# 03_ADC.net
KiCad netlist of a schematic drawn in Altium Designer
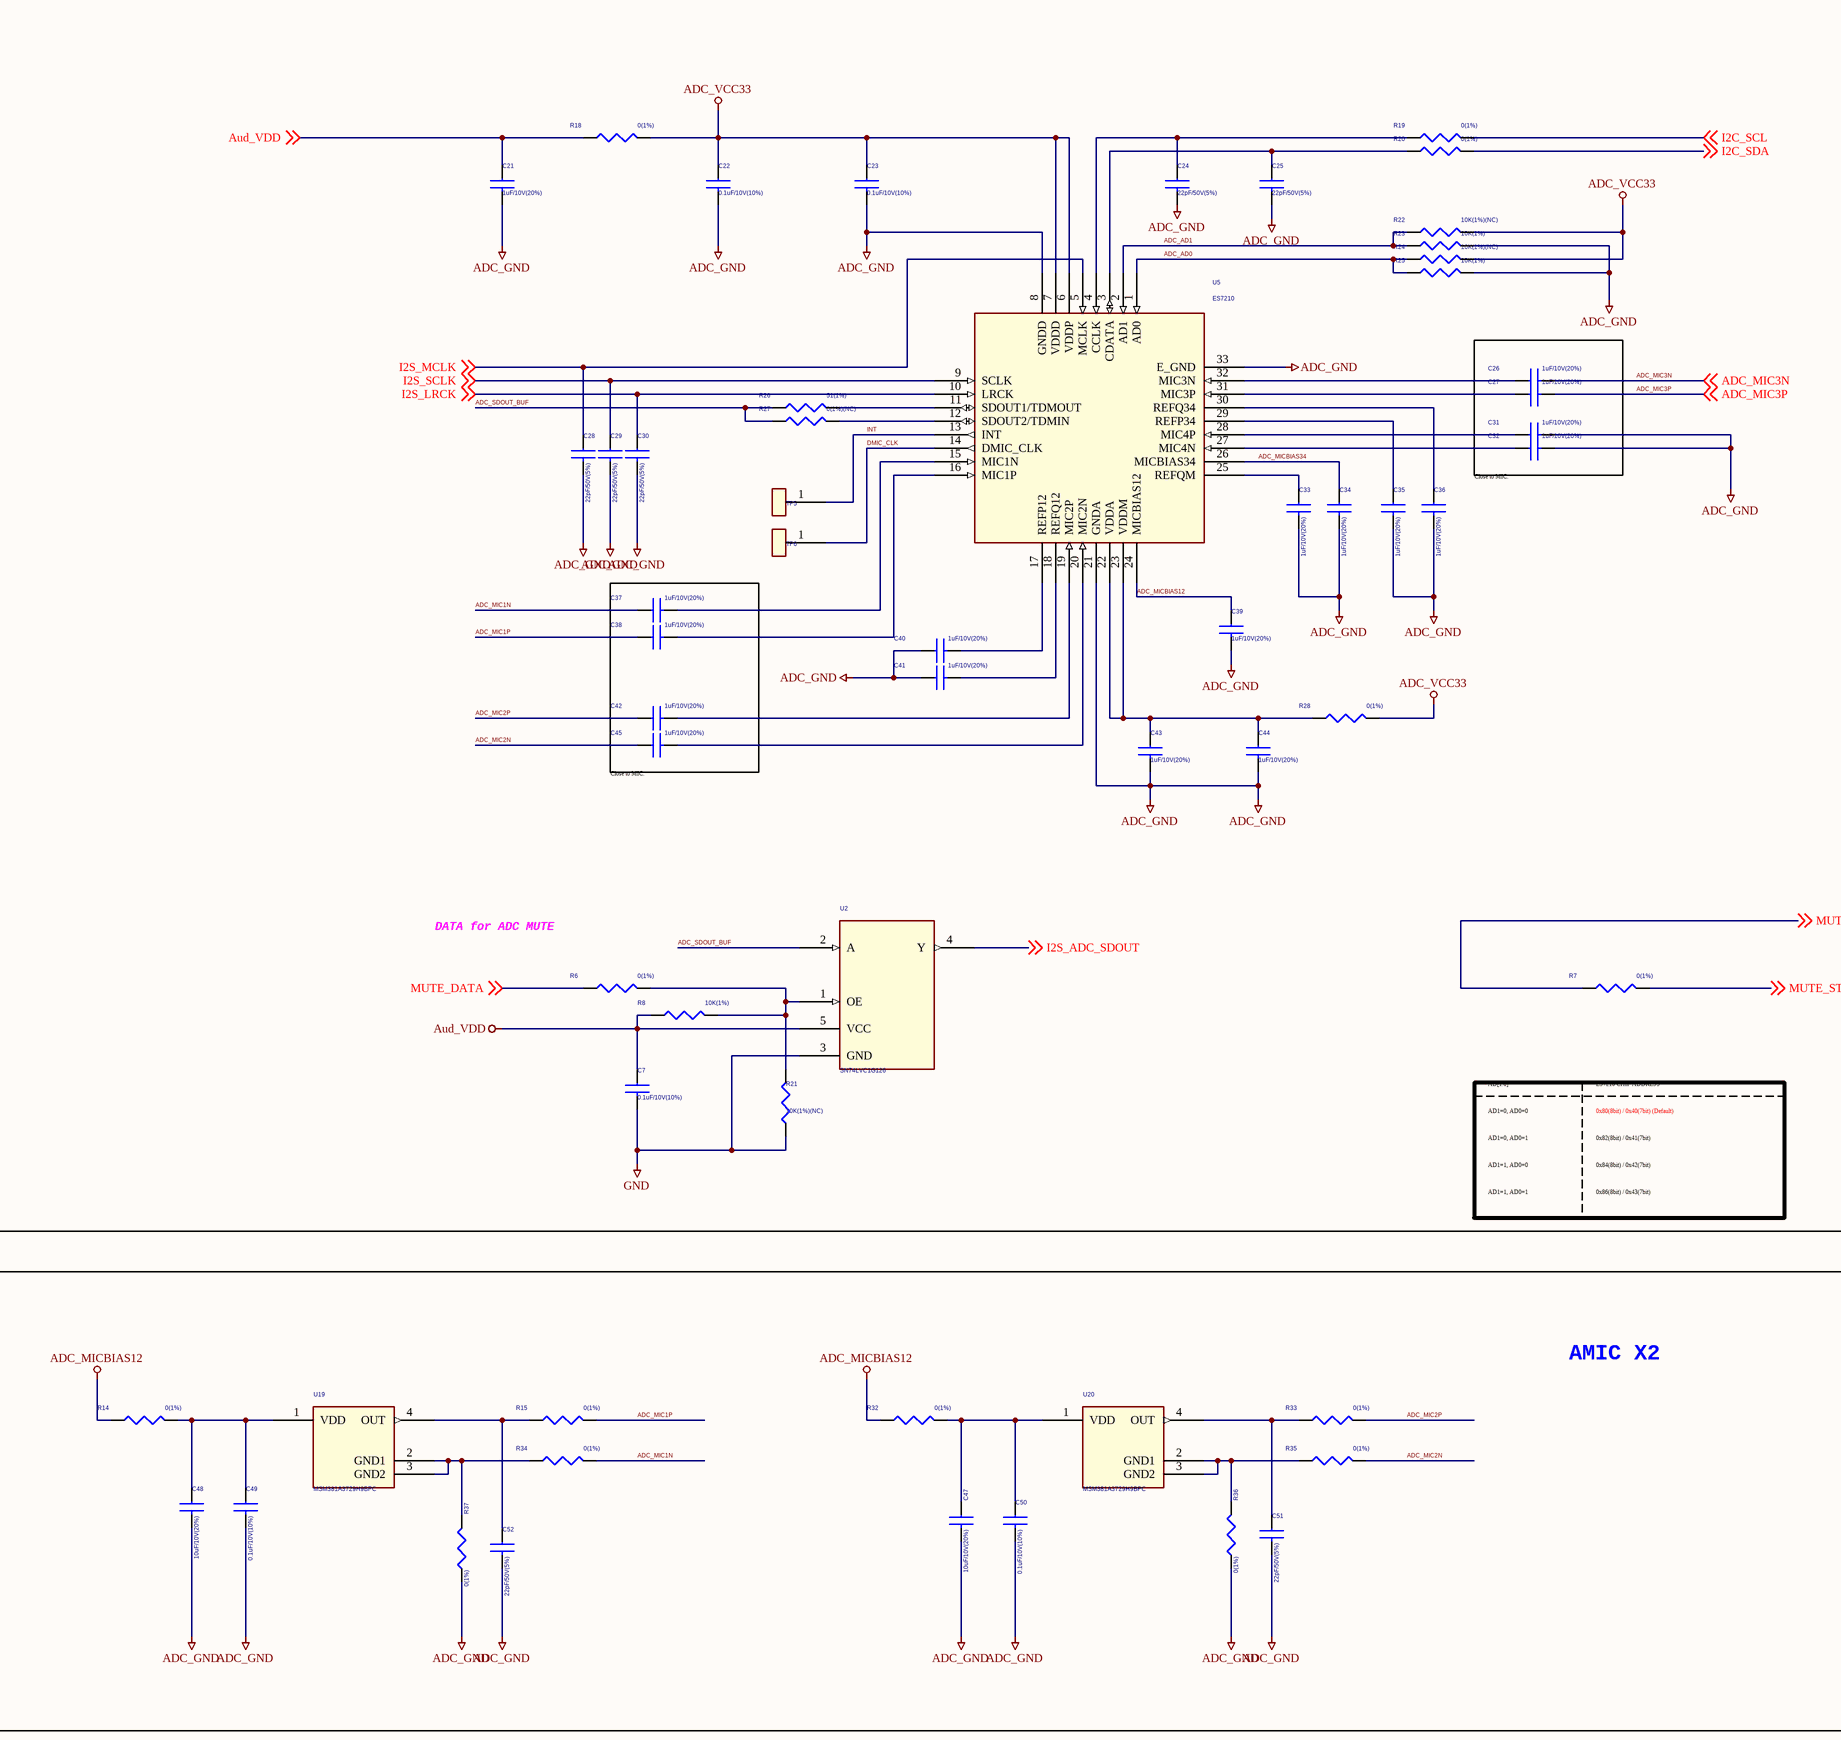
[diagram p0: 03_ADC.SchDoc, left]
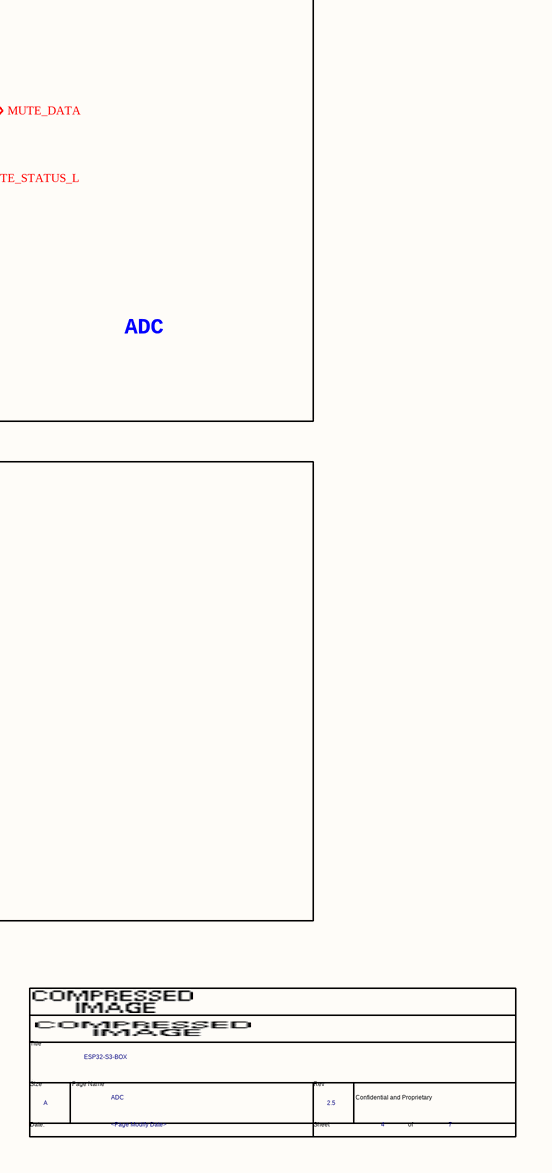
[diagram p1: 03_ADC.SchDoc, right]

(export (version "E")
  (design (tool "Eeschema 10.0.6"))
  (components
    (comp (ref "C7")
      (value "0.1uF/10V(10%)")
      (footprint "0201_C")
      (fields (field (name "PART NUMBER") "ES11025103610001"))
      (libsource (lib "*") (part "CAPACITOR"))
    )
    (comp (ref "C21")
      (value "1uF/10V(20%)")
      (footprint "0201_C")
      (fields (field (name "PART NUMBER") "ES11026103700001"))
      (libsource (lib "*") (part "CAPACITOR"))
    )
    (comp (ref "C22")
      (value "0.1uF/10V(10%)")
      (footprint "0201_C")
      (fields (field (name "PART NUMBER") "ES11025103610001"))
      (libsource (lib "*") (part "CAPACITOR"))
    )
    (comp (ref "C23")
      (value "0.1uF/10V(10%)")
      (footprint "0201_C")
      (fields (field (name "PART NUMBER") "ES11025103610001"))
      (libsource (lib "*") (part "CAPACITOR"))
    )
    (comp (ref "C24")
      (value "22pF/50V(5%)")
      (footprint "0201_C")
      (fields (field (name "PART NUMBER") "ES11021226520000"))
      (libsource (lib "*") (part "CAPACITOR"))
    )
    (comp (ref "C25")
      (value "22pF/50V(5%)")
      (footprint "0201_C")
      (fields (field (name "PART NUMBER") "ES11021226520000"))
      (libsource (lib "*") (part "CAPACITOR"))
    )
    (comp (ref "C26")
      (value "1uF/10V(20%)")
      (footprint "0201_C")
      (fields (field (name "PART NUMBER") "ES11026103700001"))
      (libsource (lib "*") (part "CAPACITOR"))
    )
    (comp (ref "C27")
      (value "1uF/10V(20%)")
      (footprint "0201_C")
      (fields (field (name "PART NUMBER") "ES11026103700001"))
      (libsource (lib "*") (part "CAPACITOR"))
    )
    (comp (ref "C28")
      (value "22pF/50V(5%)")
      (footprint "0201_C")
      (fields (field (name "PART NUMBER") "ES11021226520000"))
      (libsource (lib "*") (part "CAPACITOR"))
    )
    (comp (ref "C29")
      (value "22pF/50V(5%)")
      (footprint "0201_C")
      (fields (field (name "PART NUMBER") "ES11021226520000"))
      (libsource (lib "*") (part "CAPACITOR"))
    )
    (comp (ref "C30")
      (value "22pF/50V(5%)")
      (footprint "0201_C")
      (fields (field (name "PART NUMBER") "ES11021226520000"))
      (libsource (lib "*") (part "CAPACITOR"))
    )
    (comp (ref "C31")
      (value "1uF/10V(20%)")
      (footprint "0201_C")
      (fields (field (name "PART NUMBER") "ES11026103700001"))
      (libsource (lib "*") (part "CAPACITOR"))
    )
    (comp (ref "C32")
      (value "1uF/10V(20%)")
      (footprint "0201_C")
      (fields (field (name "PART NUMBER") "ES11026103700001"))
      (libsource (lib "*") (part "CAPACITOR"))
    )
    (comp (ref "C33")
      (value "1uF/10V(20%)")
      (footprint "0201_C")
      (fields (field (name "PART NUMBER") "ES11026103700001"))
      (libsource (lib "*") (part "CAPACITOR"))
    )
    (comp (ref "C34")
      (value "1uF/10V(20%)")
      (footprint "0201_C")
      (fields (field (name "PART NUMBER") "ES11026103700001"))
      (libsource (lib "*") (part "CAPACITOR"))
    )
    (comp (ref "C35")
      (value "1uF/10V(20%)")
      (footprint "0201_C")
      (fields (field (name "PART NUMBER") "ES11026103700001"))
      (libsource (lib "*") (part "CAPACITOR"))
    )
    (comp (ref "C36")
      (value "1uF/10V(20%)")
      (footprint "0201_C")
      (fields (field (name "PART NUMBER") "ES11026103700001"))
      (libsource (lib "*") (part "CAPACITOR"))
    )
    (comp (ref "C37")
      (value "1uF/10V(20%)")
      (footprint "0201_C")
      (fields (field (name "PART NUMBER") "ES11026103700001"))
      (libsource (lib "*") (part "CAPACITOR"))
    )
    (comp (ref "C38")
      (value "1uF/10V(20%)")
      (footprint "0201_C")
      (fields (field (name "PART NUMBER") "ES11026103700001"))
      (libsource (lib "*") (part "CAPACITOR"))
    )
    (comp (ref "C39")
      (value "1uF/10V(20%)")
      (footprint "0201_C")
      (fields (field (name "PART NUMBER") "ES11026103700001"))
      (libsource (lib "*") (part "CAPACITOR"))
    )
    (comp (ref "C40")
      (value "1uF/10V(20%)")
      (footprint "0201_C")
      (fields (field (name "PART NUMBER") "ES11026103700001"))
      (libsource (lib "*") (part "CAPACITOR"))
    )
    (comp (ref "C41")
      (value "1uF/10V(20%)")
      (footprint "0201_C")
      (fields (field (name "PART NUMBER") "ES11026103700001"))
      (libsource (lib "*") (part "CAPACITOR"))
    )
    (comp (ref "C42")
      (value "1uF/10V(20%)")
      (footprint "0201_C")
      (fields (field (name "PART NUMBER") "ES11026103700001"))
      (libsource (lib "*") (part "CAPACITOR"))
    )
    (comp (ref "C43")
      (value "1uF/10V(20%)")
      (footprint "0201_C")
      (fields (field (name "PART NUMBER") "ES11026103700001"))
      (libsource (lib "*") (part "CAPACITOR"))
    )
    (comp (ref "C44")
      (value "1uF/10V(20%)")
      (footprint "0201_C")
      (fields (field (name "PART NUMBER") "ES11026103700001"))
      (libsource (lib "*") (part "CAPACITOR"))
    )
    (comp (ref "C45")
      (value "1uF/10V(20%)")
      (footprint "0201_C")
      (fields (field (name "PART NUMBER") "ES11026103700001"))
      (libsource (lib "*") (part "CAPACITOR"))
    )
    (comp (ref "C47")
      (value "10uF/10V(20%)")
      (footprint "0402_C")
      (fields (field (name "PART NUMBER") "ES11047103700000"))
      (libsource (lib "*") (part "CAPACITOR"))
    )
    (comp (ref "C48")
      (value "10uF/10V(20%)")
      (footprint "0402_C")
      (fields (field (name "PART NUMBER") "ES11047103700000"))
      (libsource (lib "*") (part "CAPACITOR"))
    )
    (comp (ref "C49")
      (value "0.1uF/10V(10%)")
      (footprint "0201_C")
      (fields (field (name "PART NUMBER") "ES11025103610001"))
      (libsource (lib "*") (part "CAPACITOR"))
    )
    (comp (ref "C50")
      (value "0.1uF/10V(10%)")
      (footprint "0201_C")
      (fields (field (name "PART NUMBER") "ES11025103610001"))
      (libsource (lib "*") (part "CAPACITOR"))
    )
    (comp (ref "C51")
      (value "22pF/50V(5%)")
      (footprint "0201_C")
      (fields (field (name "PART NUMBER") "ES11021226520000"))
      (libsource (lib "*") (part "CAPACITOR"))
    )
    (comp (ref "C52")
      (value "22pF/50V(5%)")
      (footprint "0201_C")
      (fields (field (name "PART NUMBER") "ES11021226520000"))
      (libsource (lib "*") (part "CAPACITOR"))
    )
    (comp (ref "R6")
      (value "0(1%)")
      (footprint "0201_R")
      (fields (field (name "PART NUMBER") "ES21020000000001"))
      (libsource (lib "*") (part "RESISTOR"))
    )
    (comp (ref "R7")
      (value "0(1%)")
      (footprint "0402_R")
      (fields (field (name "PART NUMBER") "ES21040000000001"))
      (libsource (lib "*") (part "RESISTOR"))
    )
    (comp (ref "R8")
      (value "10K(1%)")
      (footprint "0201_R")
      (fields (field (name "PART NUMBER") "ES21024100000001"))
      (libsource (lib "*") (part "RESISTOR"))
    )
    (comp (ref "R14")
      (value "0(1%)")
      (footprint "0402_R")
      (fields (field (name "PART NUMBER") "ES21040000000001"))
      (libsource (lib "*") (part "RESISTOR"))
    )
    (comp (ref "R15")
      (value "0(1%)")
      (footprint "0201_R")
      (fields (field (name "PART NUMBER") "ES21020000000001"))
      (libsource (lib "*") (part "RESISTOR"))
    )
    (comp (ref "R18")
      (value "0(1%)")
      (footprint "0402_R")
      (fields (field (name "PART NUMBER") "ES21040000000001"))
      (libsource (lib "*") (part "RESISTOR"))
    )
    (comp (ref "R19")
      (value "0(1%)")
      (footprint "0201_R")
      (fields (field (name "PART NUMBER") "ES21020000000001"))
      (libsource (lib "*") (part "RESISTOR"))
    )
    (comp (ref "R20")
      (value "0(1%)")
      (footprint "0201_R")
      (fields (field (name "PART NUMBER") "ES21020000000001"))
      (libsource (lib "*") (part "RESISTOR"))
    )
    (comp (ref "R21")
      (value "10K(1%)(NC)")
      (footprint "0201_R")
      (fields (field (name "PART NUMBER") "ES21024100000001"))
      (libsource (lib "*") (part "RESISTOR"))
    )
    (comp (ref "R22")
      (value "10K(1%)(NC)")
      (footprint "0201_R")
      (fields (field (name "PART NUMBER") "ES21024100000001"))
      (libsource (lib "*") (part "RESISTOR"))
    )
    (comp (ref "R23")
      (value "10K(1%)")
      (footprint "0201_R")
      (fields (field (name "PART NUMBER") "ES21024100000001"))
      (libsource (lib "*") (part "RESISTOR"))
    )
    (comp (ref "R24")
      (value "10K(1%)(NC)")
      (footprint "0201_R")
      (fields (field (name "PART NUMBER") "ES21024100000001"))
      (libsource (lib "*") (part "RESISTOR"))
    )
    (comp (ref "R25")
      (value "10K(1%)")
      (footprint "0201_R")
      (fields (field (name "PART NUMBER") "ES21024100000001"))
      (libsource (lib "*") (part "RESISTOR"))
    )
    (comp (ref "R26")
      (value "51(1%)")
      (footprint "0201_R")
      (fields (field (name "PART NUMBER") "ES21021510000001"))
      (libsource (lib "*") (part "RESISTOR"))
    )
    (comp (ref "R27")
      (value "0(1%)(NC)")
      (footprint "0201_R")
      (fields (field (name "PART NUMBER") "ES21020000000001"))
      (libsource (lib "*") (part "RESISTOR"))
    )
    (comp (ref "R28")
      (value "0(1%)")
      (footprint "0402_R")
      (fields (field (name "PART NUMBER") "ES21040000000001"))
      (libsource (lib "*") (part "RESISTOR"))
    )
    (comp (ref "R32")
      (value "0(1%)")
      (footprint "0402_R")
      (fields (field (name "PART NUMBER") "ES21040000000001"))
      (libsource (lib "*") (part "RESISTOR"))
    )
    (comp (ref "R33")
      (value "0(1%)")
      (footprint "0201_R")
      (fields (field (name "PART NUMBER") "ES21020000000001"))
      (libsource (lib "*") (part "RESISTOR"))
    )
    (comp (ref "R34")
      (value "0(1%)")
      (footprint "0201_R")
      (fields (field (name "PART NUMBER") "ES21020000000001"))
      (libsource (lib "*") (part "RESISTOR"))
    )
    (comp (ref "R35")
      (value "0(1%)")
      (footprint "0201_R")
      (fields (field (name "PART NUMBER") "ES21020000000001"))
      (libsource (lib "*") (part "RESISTOR"))
    )
    (comp (ref "R36")
      (value "0(1%)")
      (footprint "0201_R")
      (fields (field (name "PART NUMBER") "ES21020000000001"))
      (libsource (lib "*") (part "RESISTOR"))
    )
    (comp (ref "R37")
      (value "0(1%)")
      (footprint "0201_R")
      (fields (field (name "PART NUMBER") "ES21020000000001"))
      (libsource (lib "*") (part "RESISTOR"))
    )
    (comp (ref "TP5")
      (value "TESTPOINT")
      (footprint "TPC_D40")
      (fields (field (name "PART NUMBER") "ES51990010000000"))
      (libsource (lib "*") (part "TESTPOINT"))
    )
    (comp (ref "TP6")
      (value "TESTPOINT")
      (footprint "TPC_D40")
      (fields (field (name "PART NUMBER") "ES51990010000000"))
      (libsource (lib "*") (part "TESTPOINT"))
    )
    (comp (ref "U2") (value "SN74LVC1G126") (footprint "SC-70-5") (libsource (lib "*") (part "SN74LVC1G126")))
    (comp (ref "U5")
      (value "ES7210")
      (footprint "QFN-32_5x5x05P")
      (fields (field (name "PART NUMBER") "ES41181401000000"))
      (libsource (lib "*") (part "ES7210"))
    )
    (comp (ref "U19")
      (value "MSM381A3729H9BPC")
      (footprint "MSM381")
      (fields (field (name "PART NUMBER") "ES41180800000000"))
      (libsource (lib "*") (part "MSM381A3729H9BPC"))
    )
    (comp (ref "U20")
      (value "MSM381A3729H9BPC")
      (footprint "MSM381")
      (fields (field (name "PART NUMBER") "ES41180800000000"))
      (libsource (lib "*") (part "MSM381A3729H9BPC"))
    )
  )
  (nets
    (net (code "1") (name "/ADC_AD0") (class "Default")
      (node (ref "R24") (pin "1") (pinfunction "1_1") (pintype "passive"))
      (node (ref "R25") (pin "1") (pinfunction "1_1") (pintype "passive"))
      (node (ref "U5") (pin "1") (pinfunction "AD0_1") (pintype "input"))
    )
    (net (code "2") (name "/ADC_AD1") (class "Default")
      (node (ref "R22") (pin "1") (pinfunction "1_1") (pintype "passive"))
      (node (ref "R23") (pin "1") (pinfunction "1_1") (pintype "passive"))
      (node (ref "U5") (pin "2") (pinfunction "AD1_2") (pintype "input"))
    )
    (net (code "3") (name "/ADC_MIC1N") (class "Default")
      (node (ref "C37") (pin "1") (pinfunction "1_1") (pintype "passive"))
      (node (ref "R34") (pin "2") (pinfunction "2_2") (pintype "passive"))
    )
    (net (code "4") (name "/ADC_MIC1P") (class "Default")
      (node (ref "C38") (pin "1") (pinfunction "1_1") (pintype "passive"))
      (node (ref "R15") (pin "2") (pinfunction "2_2") (pintype "passive"))
    )
    (net (code "5") (name "/ADC_MIC2N") (class "Default")
      (node (ref "C45") (pin "1") (pinfunction "1_1") (pintype "passive"))
      (node (ref "R35") (pin "2") (pinfunction "2_2") (pintype "passive"))
    )
    (net (code "6") (name "/ADC_MIC2P") (class "Default")
      (node (ref "C42") (pin "1") (pinfunction "1_1") (pintype "passive"))
      (node (ref "R33") (pin "2") (pinfunction "2_2") (pintype "passive"))
    )
    (net (code "7") (name "/ADC_MICBIAS34") (class "Default")
      (node (ref "C34") (pin "1") (pinfunction "1_1") (pintype "passive"))
      (node (ref "U5") (pin "26") (pinfunction "MICBIAS34_26") (pintype "power_in"))
    )
    (net (code "8") (name "/ADC_SDOUT_BUF") (class "Default")
      (node (ref "R26") (pin "1") (pinfunction "1_1") (pintype "passive"))
      (node (ref "R27") (pin "1") (pinfunction "1_1") (pintype "passive"))
      (node (ref "U2") (pin "2") (pinfunction "A_2") (pintype "input"))
    )
    (net (code "9") (name "/DMIC_CLK") (class "Default")
      (node (ref "TP6") (pin "1") (pinfunction "1_1") (pintype "passive"))
      (node (ref "U5") (pin "14") (pinfunction "DMIC_CLK_14") (pintype "output"))
    )
    (net (code "10") (name "/INT") (class "Default")
      (node (ref "TP5") (pin "1") (pinfunction "1_1") (pintype "passive"))
      (node (ref "U5") (pin "13") (pinfunction "INT_13") (pintype "output"))
    )
    (net (code "11") (name "ADC_GND") (class "Default")
      (node (ref "C21") (pin "2") (pinfunction "2_2") (pintype "passive"))
      (node (ref "C22") (pin "2") (pinfunction "2_2") (pintype "passive"))
      (node (ref "C23") (pin "2") (pinfunction "2_2") (pintype "passive"))
      (node (ref "C24") (pin "2") (pinfunction "2_2") (pintype "passive"))
      (node (ref "C25") (pin "2") (pinfunction "2_2") (pintype "passive"))
      (node (ref "C28") (pin "2") (pinfunction "2_2") (pintype "passive"))
      (node (ref "C29") (pin "2") (pinfunction "2_2") (pintype "passive"))
      (node (ref "C30") (pin "2") (pinfunction "2_2") (pintype "passive"))
      (node (ref "C31") (pin "2") (pinfunction "2_2") (pintype "passive"))
      (node (ref "C32") (pin "2") (pinfunction "2_2") (pintype "passive"))
      (node (ref "C33") (pin "2") (pinfunction "2_2") (pintype "passive"))
      (node (ref "C34") (pin "2") (pinfunction "2_2") (pintype "passive"))
      (node (ref "C35") (pin "2") (pinfunction "2_2") (pintype "passive"))
      (node (ref "C36") (pin "2") (pinfunction "2_2") (pintype "passive"))
      (node (ref "C39") (pin "2") (pinfunction "2_2") (pintype "passive"))
      (node (ref "C40") (pin "1") (pinfunction "1_1") (pintype "passive"))
      (node (ref "C41") (pin "1") (pinfunction "1_1") (pintype "passive"))
      (node (ref "C43") (pin "2") (pinfunction "2_2") (pintype "passive"))
      (node (ref "C44") (pin "2") (pinfunction "2_2") (pintype "passive"))
      (node (ref "C47") (pin "2") (pinfunction "2_2") (pintype "passive"))
      (node (ref "C48") (pin "2") (pinfunction "2_2") (pintype "passive"))
      (node (ref "C49") (pin "2") (pinfunction "2_2") (pintype "passive"))
      (node (ref "C50") (pin "2") (pinfunction "2_2") (pintype "passive"))
      (node (ref "C51") (pin "2") (pinfunction "2_2") (pintype "passive"))
      (node (ref "C52") (pin "2") (pinfunction "2_2") (pintype "passive"))
      (node (ref "R23") (pin "2") (pinfunction "2_2") (pintype "passive"))
      (node (ref "R25") (pin "2") (pinfunction "2_2") (pintype "passive"))
      (node (ref "R36") (pin "1") (pinfunction "1_1") (pintype "passive"))
      (node (ref "R37") (pin "1") (pinfunction "1_1") (pintype "passive"))
      (node (ref "U5") (pin "21") (pinfunction "GNDA_21") (pintype "power_in"))
      (node (ref "U5") (pin "33") (pinfunction "E_GND_33") (pintype "power_in"))
      (node (ref "U5") (pin "8") (pinfunction "GNDD_8") (pintype "power_in"))
    )
    (net (code "12") (name "ADC_MIC3N") (class "Default")
      (node (ref "C26") (pin "2") (pinfunction "2_2") (pintype "passive"))
    )
    (net (code "13") (name "ADC_MIC3P") (class "Default")
      (node (ref "C27") (pin "2") (pinfunction "2_2") (pintype "passive"))
    )
    (net (code "14") (name "ADC_MICBIAS12") (class "Default")
      (node (ref "C39") (pin "1") (pinfunction "1_1") (pintype "passive"))
      (node (ref "R14") (pin "1") (pinfunction "1_1") (pintype "passive"))
      (node (ref "R32") (pin "1") (pinfunction "1_1") (pintype "passive"))
      (node (ref "U5") (pin "24") (pinfunction "MICBIAS12_24") (pintype "power_in"))
    )
    (net (code "15") (name "ADC_VCC33") (class "Default")
      (node (ref "C22") (pin "1") (pinfunction "1_1") (pintype "passive"))
      (node (ref "C23") (pin "1") (pinfunction "1_1") (pintype "passive"))
      (node (ref "R18") (pin "2") (pinfunction "2_2") (pintype "passive"))
      (node (ref "R22") (pin "2") (pinfunction "2_2") (pintype "passive"))
      (node (ref "R24") (pin "2") (pinfunction "2_2") (pintype "passive"))
      (node (ref "R28") (pin "2") (pinfunction "2_2") (pintype "passive"))
      (node (ref "U5") (pin "6") (pinfunction "VDDP_6") (pintype "power_in"))
      (node (ref "U5") (pin "7") (pinfunction "VDDD_7") (pintype "power_in"))
    )
    (net (code "16") (name "Aud_VDD") (class "Default")
      (node (ref "C21") (pin "1") (pinfunction "1_1") (pintype "passive"))
      (node (ref "C7") (pin "1") (pinfunction "1_1") (pintype "passive"))
      (node (ref "R18") (pin "1") (pinfunction "1_1") (pintype "passive"))
      (node (ref "R8") (pin "1") (pinfunction "1_1") (pintype "passive"))
      (node (ref "U2") (pin "5") (pinfunction "VCC_5") (pintype "power_in"))
    )
    (net (code "17") (name "GND") (class "Default")
      (node (ref "C7") (pin "2") (pinfunction "2_2") (pintype "passive"))
      (node (ref "R21") (pin "1") (pinfunction "1_1") (pintype "passive"))
      (node (ref "U2") (pin "3") (pinfunction "GND_3") (pintype "power_in"))
    )
    (net (code "18") (name "I2C_SCL") (class "Default")
      (node (ref "R19") (pin "2") (pinfunction "2_2") (pintype "passive"))
    )
    (net (code "19") (name "I2C_SDA") (class "Default")
      (node (ref "R20") (pin "2") (pinfunction "2_2") (pintype "passive"))
    )
    (net (code "20") (name "I2S_ADC_SDOUT") (class "Default")
      (node (ref "U2") (pin "4") (pinfunction "Y_4") (pintype "output"))
    )
    (net (code "21") (name "I2S_LRCK") (class "Default")
      (node (ref "C30") (pin "1") (pinfunction "1_1") (pintype "passive"))
      (node (ref "U5") (pin "10") (pinfunction "LRCK_10") (pintype "input"))
    )
    (net (code "22") (name "I2S_MCLK") (class "Default")
      (node (ref "C28") (pin "1") (pinfunction "1_1") (pintype "passive"))
      (node (ref "U5") (pin "5") (pinfunction "MCLK_5") (pintype "input"))
    )
    (net (code "23") (name "I2S_SCLK") (class "Default")
      (node (ref "C29") (pin "1") (pinfunction "1_1") (pintype "passive"))
      (node (ref "U5") (pin "9") (pinfunction "SCLK_9") (pintype "input"))
    )
    (net (code "24") (name "MUTE_DATA") (class "Default")
      (node (ref "R6") (pin "1") (pinfunction "1_1") (pintype "passive"))
      (node (ref "R7") (pin "1") (pinfunction "1_1") (pintype "passive"))
    )
    (net (code "25") (name "MUTE_STATUS_L") (class "Default")
      (node (ref "R7") (pin "2") (pinfunction "2_2") (pintype "passive"))
    )
    (net (code "26") (name "Net-(U2-OE)") (class "Default")
      (node (ref "R21") (pin "2") (pinfunction "2_2") (pintype "passive"))
      (node (ref "R6") (pin "2") (pinfunction "2_2") (pintype "passive"))
      (node (ref "R8") (pin "2") (pinfunction "2_2") (pintype "passive"))
      (node (ref "U2") (pin "1") (pinfunction "OE_1") (pintype "input"))
    )
    (net (code "27") (name "Net-(U5-CCLK)") (class "Default")
      (node (ref "C24") (pin "1") (pinfunction "1_1") (pintype "passive"))
      (node (ref "R19") (pin "1") (pinfunction "1_1") (pintype "passive"))
      (node (ref "U5") (pin "4") (pinfunction "CCLK_4") (pintype "input"))
    )
    (net (code "28") (name "Net-(U5-CDATA)") (class "Default")
      (node (ref "C25") (pin "1") (pinfunction "1_1") (pintype "passive"))
      (node (ref "R20") (pin "1") (pinfunction "1_1") (pintype "passive"))
      (node (ref "U5") (pin "3") (pinfunction "CDATA_3") (pintype "bidirectional"))
    )
    (net (code "29") (name "Net-(U5-MIC1N)") (class "Default")
      (node (ref "C37") (pin "2") (pinfunction "2_2") (pintype "passive"))
      (node (ref "U5") (pin "15") (pinfunction "MIC1N_15") (pintype "input"))
    )
    (net (code "30") (name "Net-(U5-MIC1P)") (class "Default")
      (node (ref "C38") (pin "2") (pinfunction "2_2") (pintype "passive"))
      (node (ref "U5") (pin "16") (pinfunction "MIC1P_16") (pintype "input"))
    )
    (net (code "31") (name "Net-(U5-MIC2N)") (class "Default")
      (node (ref "C45") (pin "2") (pinfunction "2_2") (pintype "passive"))
      (node (ref "U5") (pin "20") (pinfunction "MIC2N_20") (pintype "input"))
    )
    (net (code "32") (name "Net-(U5-MIC2P)") (class "Default")
      (node (ref "C42") (pin "2") (pinfunction "2_2") (pintype "passive"))
      (node (ref "U5") (pin "19") (pinfunction "MIC2P_19") (pintype "input"))
    )
    (net (code "33") (name "Net-(U5-MIC3N)") (class "Default")
      (node (ref "C26") (pin "1") (pinfunction "1_1") (pintype "passive"))
      (node (ref "U5") (pin "32") (pinfunction "MIC3N_32") (pintype "input"))
    )
    (net (code "34") (name "Net-(U5-MIC3P)") (class "Default")
      (node (ref "C27") (pin "1") (pinfunction "1_1") (pintype "passive"))
      (node (ref "U5") (pin "31") (pinfunction "MIC3P_31") (pintype "input"))
    )
    (net (code "35") (name "Net-(U5-MIC4N)") (class "Default")
      (node (ref "C32") (pin "1") (pinfunction "1_1") (pintype "passive"))
      (node (ref "U5") (pin "27") (pinfunction "MIC4N_27") (pintype "input"))
    )
    (net (code "36") (name "Net-(U5-MIC4P)") (class "Default")
      (node (ref "C31") (pin "1") (pinfunction "1_1") (pintype "passive"))
      (node (ref "U5") (pin "28") (pinfunction "MIC4P_28") (pintype "input"))
    )
    (net (code "37") (name "Net-(U5-REFP12)") (class "Default")
      (node (ref "C40") (pin "2") (pinfunction "2_2") (pintype "passive"))
      (node (ref "U5") (pin "17") (pinfunction "REFP12_17") (pintype "power_in"))
    )
    (net (code "38") (name "Net-(U5-REFP34)") (class "Default")
      (node (ref "C35") (pin "1") (pinfunction "1_1") (pintype "passive"))
      (node (ref "U5") (pin "29") (pinfunction "REFP34_29") (pintype "power_in"))
    )
    (net (code "39") (name "Net-(U5-REFQ12)") (class "Default")
      (node (ref "C41") (pin "2") (pinfunction "2_2") (pintype "passive"))
      (node (ref "U5") (pin "18") (pinfunction "REFQ12_18") (pintype "power_in"))
    )
    (net (code "40") (name "Net-(U5-REFQ34)") (class "Default")
      (node (ref "C36") (pin "1") (pinfunction "1_1") (pintype "passive"))
      (node (ref "U5") (pin "30") (pinfunction "REFQ34_30") (pintype "power_in"))
    )
    (net (code "41") (name "Net-(U5-REFQM)") (class "Default")
      (node (ref "C33") (pin "1") (pinfunction "1_1") (pintype "passive"))
      (node (ref "U5") (pin "25") (pinfunction "REFQM_25") (pintype "power_in"))
    )
    (net (code "42") (name "Net-(U5-SDOUT1{slash}TDMOUT)") (class "Default")
      (node (ref "R26") (pin "2") (pinfunction "2_2") (pintype "passive"))
      (node (ref "U5") (pin "11") (pinfunction "SDOUT1/TDMOUT_11") (pintype "bidirectional"))
    )
    (net (code "43") (name "Net-(U5-SDOUT2{slash}TDMIN)") (class "Default")
      (node (ref "R27") (pin "2") (pinfunction "2_2") (pintype "passive"))
      (node (ref "U5") (pin "12") (pinfunction "SDOUT2/TDMIN_12") (pintype "bidirectional"))
    )
    (net (code "44") (name "Net-(U5-VDDA)") (class "Default")
      (node (ref "C43") (pin "1") (pinfunction "1_1") (pintype "passive"))
      (node (ref "C44") (pin "1") (pinfunction "1_1") (pintype "passive"))
      (node (ref "R28") (pin "1") (pinfunction "1_1") (pintype "passive"))
      (node (ref "U5") (pin "22") (pinfunction "VDDA_22") (pintype "power_in"))
      (node (ref "U5") (pin "23") (pinfunction "VDDM_23") (pintype "power_in"))
    )
    (net (code "45") (name "Net-(U19-GND1)") (class "Default")
      (node (ref "R34") (pin "1") (pinfunction "1_1") (pintype "passive"))
      (node (ref "R37") (pin "2") (pinfunction "2_2") (pintype "passive"))
      (node (ref "U19") (pin "2") (pinfunction "GND1_2") (pintype "power_in"))
      (node (ref "U19") (pin "3") (pinfunction "GND2_3") (pintype "power_in"))
    )
    (net (code "46") (name "Net-(U19-OUT)") (class "Default")
      (node (ref "C52") (pin "1") (pinfunction "1_1") (pintype "passive"))
      (node (ref "R15") (pin "1") (pinfunction "1_1") (pintype "passive"))
      (node (ref "U19") (pin "4") (pinfunction "OUT_4") (pintype "output"))
    )
    (net (code "47") (name "Net-(U19-VDD)") (class "Default")
      (node (ref "C48") (pin "1") (pinfunction "1_1") (pintype "passive"))
      (node (ref "C49") (pin "1") (pinfunction "1_1") (pintype "passive"))
      (node (ref "R14") (pin "2") (pinfunction "2_2") (pintype "passive"))
      (node (ref "U19") (pin "1") (pinfunction "VDD_1") (pintype "power_in"))
    )
    (net (code "48") (name "Net-(U20-GND1)") (class "Default")
      (node (ref "R35") (pin "1") (pinfunction "1_1") (pintype "passive"))
      (node (ref "R36") (pin "2") (pinfunction "2_2") (pintype "passive"))
      (node (ref "U20") (pin "2") (pinfunction "GND1_2") (pintype "power_in"))
      (node (ref "U20") (pin "3") (pinfunction "GND2_3") (pintype "power_in"))
    )
    (net (code "49") (name "Net-(U20-OUT)") (class "Default")
      (node (ref "C51") (pin "1") (pinfunction "1_1") (pintype "passive"))
      (node (ref "R33") (pin "1") (pinfunction "1_1") (pintype "passive"))
      (node (ref "U20") (pin "4") (pinfunction "OUT_4") (pintype "output"))
    )
    (net (code "50") (name "Net-(U20-VDD)") (class "Default")
      (node (ref "C47") (pin "1") (pinfunction "1_1") (pintype "passive"))
      (node (ref "C50") (pin "1") (pinfunction "1_1") (pintype "passive"))
      (node (ref "R32") (pin "2") (pinfunction "2_2") (pintype "passive"))
      (node (ref "U20") (pin "1") (pinfunction "VDD_1") (pintype "power_in"))
    )
  )
)
